# FUN.net
KiCad netlist of a schematic drawn in Altium Designer
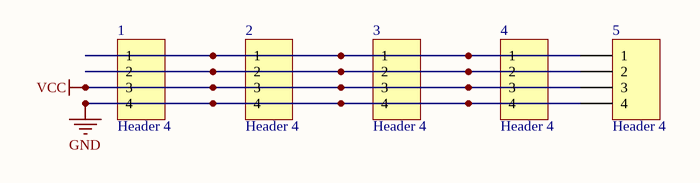
[diagram p0: FUN.SchDoc]

(export (version "E")
  (design (tool "Eeschema 10.0.6"))
  (components
    (comp (ref "1")
      (value "Header 4")
      (footprint "HDR1X4")
      (description "Header, 4-Pin")
      (fields (field (name "PUBLISHER") "Altium Limited"))
      (libsource (lib "Miscellaneous Connectors") (part "Header 4"))
    )
    (comp (ref "2")
      (value "Header 4")
      (footprint "HDR1X4")
      (description "Header, 4-Pin")
      (fields (field (name "PUBLISHER") "Altium Limited"))
      (libsource (lib "Miscellaneous Connectors") (part "Header 4"))
    )
    (comp (ref "3")
      (value "Header 4")
      (footprint "HDR1X4")
      (description "Header, 4-Pin")
      (fields (field (name "PUBLISHER") "Altium Limited"))
      (libsource (lib "Miscellaneous Connectors") (part "Header 4"))
    )
    (comp (ref "4")
      (value "Header 4")
      (footprint "HDR1X4")
      (description "Header, 4-Pin")
      (fields (field (name "PUBLISHER") "Altium Limited"))
      (libsource (lib "Miscellaneous Connectors") (part "Header 4"))
    )
    (comp (ref "5")
      (value "Header 4")
      (footprint "HDR1X4")
      (description "Header, 4-Pin")
      (fields (field (name "PUBLISHER") "Altium Limited"))
      (libsource (lib "Miscellaneous Connectors") (part "Header 4"))
    )
  )
  (nets
    (net (code "1") (name "GND") (class "Default")
      (node (ref "1") (pin "4") (pinfunction "4_4") (pintype "passive"))
      (node (ref "2") (pin "4") (pinfunction "4_4") (pintype "passive"))
      (node (ref "3") (pin "4") (pinfunction "4_4") (pintype "passive"))
      (node (ref "4") (pin "4") (pinfunction "4_4") (pintype "passive"))
      (node (ref "5") (pin "4") (pinfunction "4_4") (pintype "passive"))
    )
    (net (code "2") (name "Net-(1-Pad1)") (class "Default")
      (node (ref "1") (pin "1") (pinfunction "1_1") (pintype "passive"))
      (node (ref "2") (pin "1") (pinfunction "1_1") (pintype "passive"))
      (node (ref "3") (pin "1") (pinfunction "1_1") (pintype "passive"))
      (node (ref "4") (pin "1") (pinfunction "1_1") (pintype "passive"))
      (node (ref "5") (pin "1") (pinfunction "1_1") (pintype "passive"))
    )
    (net (code "3") (name "Net-(1-Pad2)") (class "Default")
      (node (ref "1") (pin "2") (pinfunction "2_2") (pintype "passive"))
      (node (ref "2") (pin "2") (pinfunction "2_2") (pintype "passive"))
      (node (ref "3") (pin "2") (pinfunction "2_2") (pintype "passive"))
      (node (ref "4") (pin "2") (pinfunction "2_2") (pintype "passive"))
      (node (ref "5") (pin "2") (pinfunction "2_2") (pintype "passive"))
    )
    (net (code "4") (name "VCC") (class "Default")
      (node (ref "1") (pin "3") (pinfunction "3_3") (pintype "passive"))
      (node (ref "2") (pin "3") (pinfunction "3_3") (pintype "passive"))
      (node (ref "3") (pin "3") (pinfunction "3_3") (pintype "passive"))
      (node (ref "4") (pin "3") (pinfunction "3_3") (pintype "passive"))
      (node (ref "5") (pin "3") (pinfunction "3_3") (pintype "passive"))
    )
  )
)
